# power_source.net
KiCad netlist of a schematic drawn in Altium Designer
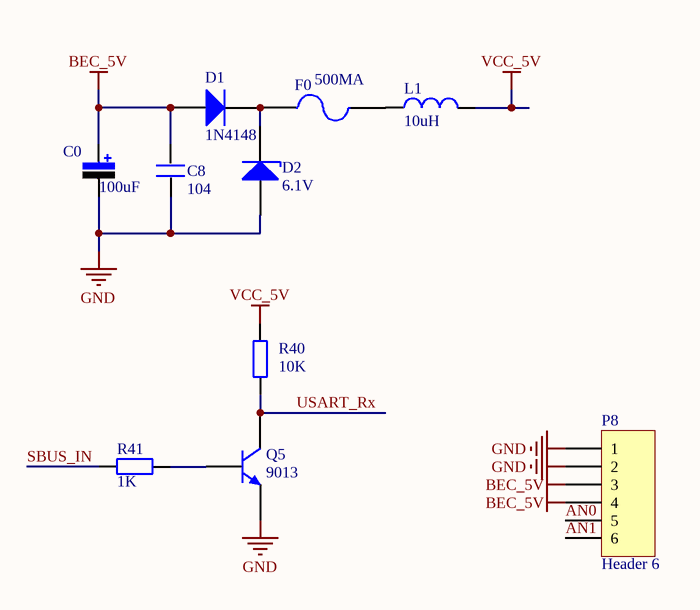
[diagram p0: power source.SchDoc]

(export (version "E")
  (design (tool "Eeschema 10.0.6"))
  (components
    (comp (ref "C0")
      (value "100uF")
      (footprint "DIODE_SMC")
      (description "插件电解电容")
      (fields (field (name "Comment") "Cap-Pol-ER") (field (name "PUBLISHER") "Altium Limited"))
      (libsource (lib "Fszhang") (part "Cap-Pol-ER"))
    )
    (comp (ref "C8") (value "104") (footprint "0805") (libsource (lib "OLED模块封装库") (part "C")))
    (comp (ref "D1")
      (value "1N4148")
      (footprint "DIODE_SOP")
      (description "二极管")
      (fields (field (name "PUBLISHER") "Altium Limited"))
      (libsource (lib "Fszhang") (part "Diode"))
    )
    (comp (ref "D2")
      (value "6.1V")
      (footprint "DIODE_SOP")
      (description "稳压二极管")
      (fields (field (name "Comment") "Diode-Z") (field (name "PUBLISHER") "Altium Limited"))
      (libsource (lib "Fszhang") (part "Diode-Z"))
    )
    (comp (ref "F0")
      (value "500MA")
      (footprint "Miscellaneous Devices:1812")
      (description "Fuse")
      (fields (field (name "PUBLISHER") "Altium Limited"))
      (libsource (lib "Miscellaneous Devices") (part "Fuse 2"))
    )
    (comp (ref "L1")
      (value "10uH")
      (footprint "1206")
      (description "电感")
      (fields (field (name "Comment") "Inductor") (field (name "PUBLISHER") "Altium Limited"))
      (libsource (lib "Fszhang") (part "Inductor"))
    )
    (comp (ref "P8")
      (value "Header 6")
      (footprint "HDR1X6")
      (description "Header, 6-Pin")
      (fields (field (name "PUBLISHER") "Altium Limited"))
      (libsource (lib "Miscellaneous Connectors") (part "Header 6"))
    )
    (comp (ref "Q5")
      (value "9013")
      (footprint "Miscellaneous Devices:SOT23_L")
      (description "NPN General Purpose Amplifier")
      (fields (field (name "PUBLISHER") "Altium Limited"))
      (libsource (lib "Miscellaneous Devices") (part "2N3904"))
    )
    (comp (ref "R40")
      (value "10K")
      (footprint "3.5TFTLCD封装库:0805")
      (description "Resistor")
      (fields (field (name "Comment") "Res2") (field (name "PUBLISHER") "Altium Limited"))
      (libsource (lib "") (part "Res2_1"))
    )
    (comp (ref "R41")
      (value "1K")
      (footprint "3.5TFTLCD封装库:0805")
      (description "Resistor")
      (fields (field (name "Comment") "Res2") (field (name "PUBLISHER") "Altium Limited"))
      (libsource (lib "Miscellaneous Devices") (part "Res2"))
    )
  )
  (nets
    (net (code "1") (name "/AN0") (class "Default")
      (node (ref "P8") (pin "5") (pinfunction "5_5") (pintype "passive"))
    )
    (net (code "2") (name "/AN1") (class "Default")
      (node (ref "P8") (pin "6") (pinfunction "6_6") (pintype "passive"))
    )
    (net (code "3") (name "/SBUS_IN") (class "Default")
      (node (ref "R41") (pin "2") (pinfunction "2_2") (pintype "passive"))
    )
    (net (code "4") (name "/USART_Rx") (class "Default")
      (node (ref "Q5") (pin "1") (pinfunction "E_1") (pintype "passive"))
      (node (ref "R40") (pin "1") (pinfunction "1_1") (pintype "passive"))
    )
    (net (code "5") (name "BEC_5V") (class "Default")
      (node (ref "C0") (pin "1") (pinfunction "1_1") (pintype "passive"))
      (node (ref "C8") (pin "1") (pintype "passive"))
      (node (ref "D1") (pin "1") (pinfunction "A_1") (pintype "passive"))
      (node (ref "P8") (pin "3") (pinfunction "3_3") (pintype "passive"))
      (node (ref "P8") (pin "4") (pinfunction "4_4") (pintype "passive"))
    )
    (net (code "6") (name "GND") (class "Default")
      (node (ref "C0") (pin "2") (pinfunction "2_2") (pintype "passive"))
      (node (ref "C8") (pin "2") (pintype "passive"))
      (node (ref "D2") (pin "1") (pinfunction "A_1") (pintype "passive"))
      (node (ref "P8") (pin "1") (pinfunction "1_1") (pintype "passive"))
      (node (ref "P8") (pin "2") (pinfunction "2_2") (pintype "passive"))
      (node (ref "Q5") (pin "3") (pinfunction "C_3") (pintype "passive"))
    )
    (net (code "7") (name "Net-(D1-K)") (class "Default")
      (node (ref "D1") (pin "2") (pinfunction "K_2") (pintype "passive"))
      (node (ref "D2") (pin "2") (pinfunction "K_2") (pintype "passive"))
      (node (ref "F0") (pin "1") (pinfunction "1_1") (pintype "passive"))
    )
    (net (code "8") (name "Net-(F0-Pad2)") (class "Default")
      (node (ref "F0") (pin "2") (pinfunction "2_2") (pintype "passive"))
      (node (ref "L1") (pin "1") (pinfunction "1_1") (pintype "passive"))
    )
    (net (code "9") (name "Net-(Q5-B)") (class "Default")
      (node (ref "Q5") (pin "2") (pinfunction "B_2") (pintype "passive"))
      (node (ref "R41") (pin "1") (pinfunction "1_1") (pintype "passive"))
    )
    (net (code "10") (name "VCC_5V") (class "Default")
      (node (ref "L1") (pin "2") (pinfunction "2_2") (pintype "passive"))
      (node (ref "R40") (pin "2") (pinfunction "2_2") (pintype "passive"))
    )
  )
)
